# SCH_Irrigador-Autom_tico-Amanco_2026-02-.net
KiCad netlist of a schematic drawn in EasyEDA
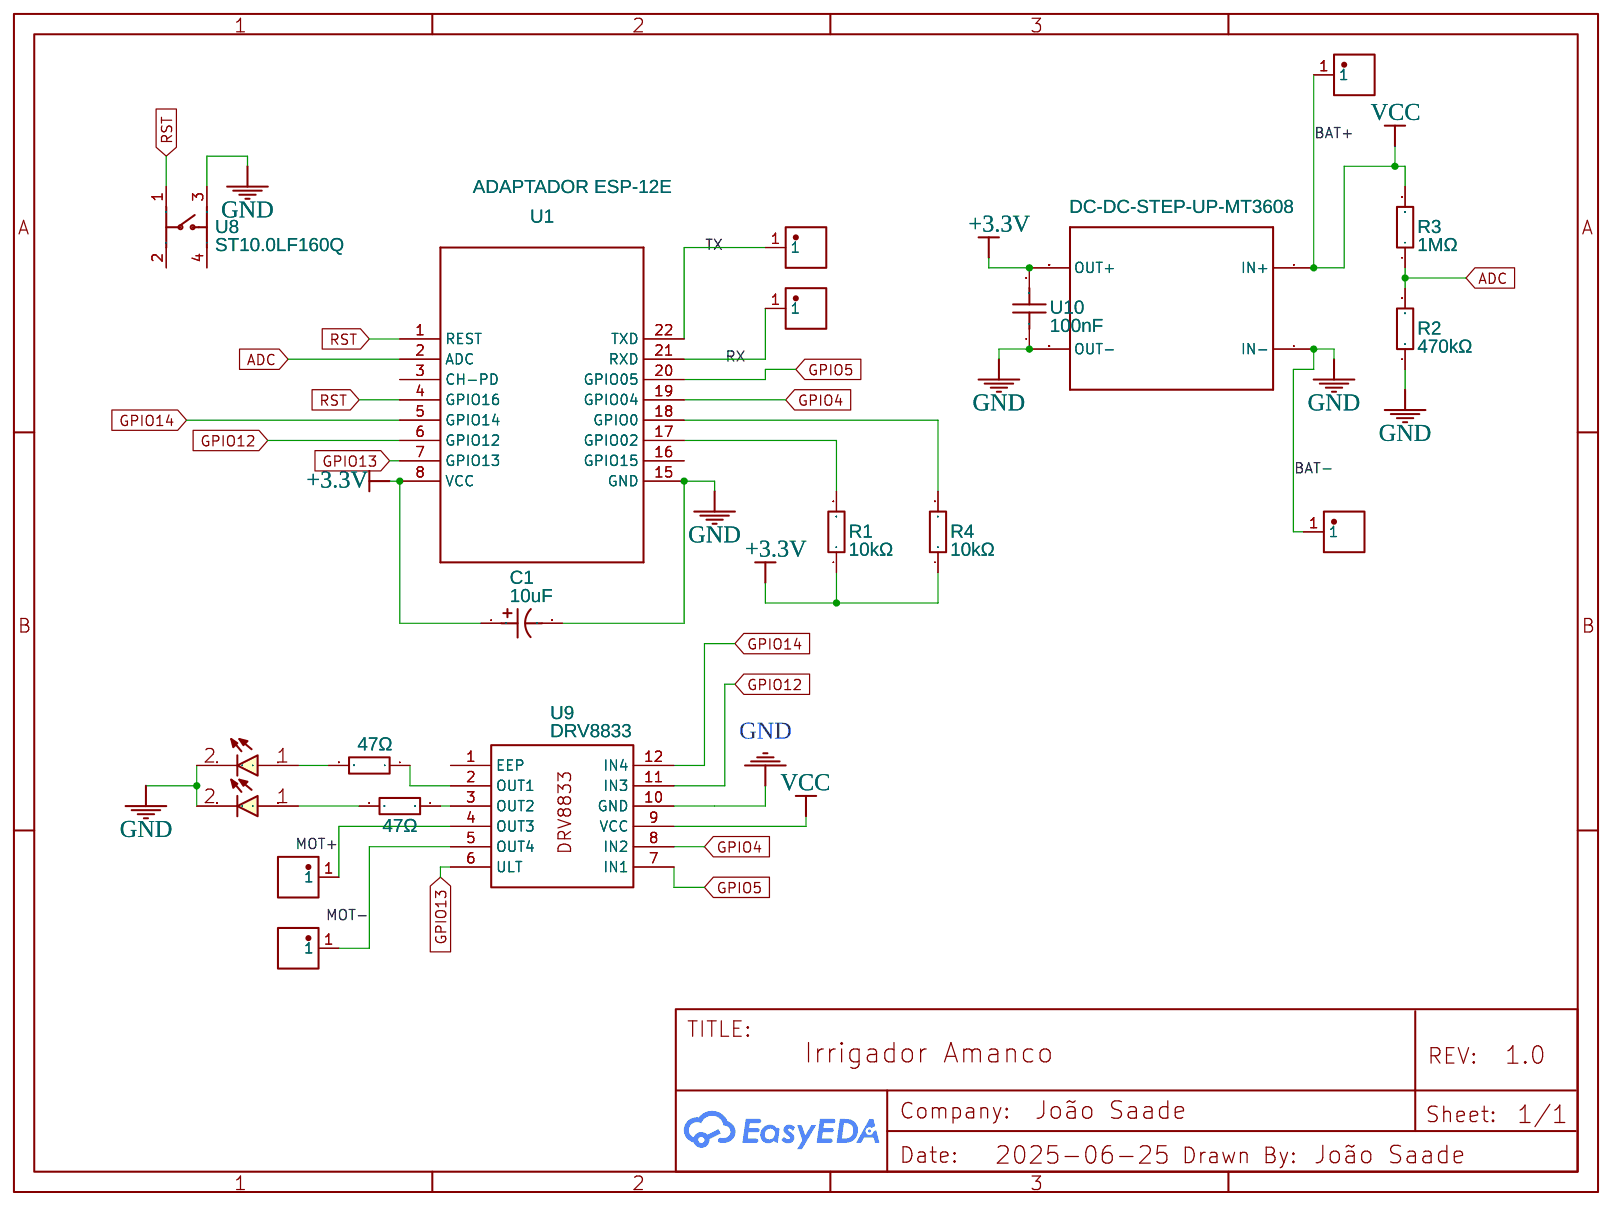
[diagram p0: schematic sheet]

(export (version "E")
  (design (tool "Eeschema 10.0.6"))
  (components
    (comp (ref "1") (value "DC-DC-STEP-UP-MT3608") (libsource (lib "") (part "DC-DC-STEP-UP-MT3608")))
    (comp (ref "C1")
      (value "10uF")
      (fields
        (field (name "Manufacturer Part") "NXA50V10M5*11 2.5TP")
        (field (name "Manufacturer") "SAMYOUNG(韩国三莹)")
      )
      (libsource (lib "") (part "NXA50V10M5*11 2.5TP"))
    )
    (comp (ref "LED1") (value "LED-5MM-GRE") (libsource (lib "") (part "LED-5MM-GRE")))
    (comp (ref "LED2") (value "LED-5MM-RED") (libsource (lib "") (part "LED-5MM-RED")))
    (comp (ref "R1")
      (value "10kΩ")
      (fields
        (field (name "Manufacturer Part") "CF1/4W-110KΩ±5% T52")
        (field (name "Manufacturer") "CCO(千志电子)")
      )
      (libsource (lib "") (part "CF1/4W-110KΩ±5% T52"))
    )
    (comp (ref "R2")
      (value "470kΩ")
      (fields
        (field (name "Manufacturer Part") "CF1/4W-110KΩ±5% T52")
        (field (name "Manufacturer") "CCO(千志电子)")
      )
      (libsource (lib "") (part "CF1/4W-110KΩ±5% T52"))
    )
    (comp (ref "R3")
      (value "1MΩ")
      (fields
        (field (name "Manufacturer Part") "CF1/4W-110KΩ±5% T52")
        (field (name "Manufacturer") "CCO(千志电子)")
      )
      (libsource (lib "") (part "CF1/4W-110KΩ±5% T52"))
    )
    (comp (ref "R4")
      (value "10kΩ")
      (fields
        (field (name "Manufacturer Part") "CF1/4W-110KΩ±5% T52")
        (field (name "Manufacturer") "CCO(千志电子)")
      )
      (libsource (lib "") (part "CF1/4W-110KΩ±5% T52"))
    )
    (comp (ref "R5")
      (value "47Ω")
      (fields
        (field (name "Manufacturer Part") "CF1/4W-110KΩ±5% T52")
        (field (name "Manufacturer") "CCO(千志电子)")
      )
      (libsource (lib "") (part "CF1/4W-110KΩ±5% T52_1"))
    )
    (comp (ref "R6")
      (value "47Ω")
      (fields
        (field (name "Manufacturer Part") "CF1/4W-110KΩ±5% T52")
        (field (name "Manufacturer") "CCO(千志电子)")
      )
      (libsource (lib "") (part "CF1/4W-110KΩ±5% T52_1"))
    )
    (comp (ref "U1") (value "ADAPTADOR ESP-12E") (libsource (lib "") (part "ADAPTADOR ESP-12E")))
    (comp (ref "U2")
      (value "P70-2200045")
      (fields (field (name "Manufacturer") "Harwin"))
      (libsource (lib "") (part "P70-2200045"))
    )
    (comp (ref "U3")
      (value "P70-2200045")
      (fields (field (name "Manufacturer") "Harwin"))
      (libsource (lib "") (part "P70-2200045"))
    )
    (comp (ref "U4")
      (value "P70-2200045")
      (fields (field (name "Manufacturer") "Harwin"))
      (libsource (lib "") (part "P70-2200045"))
    )
    (comp (ref "U5")
      (value "P70-2200045")
      (fields (field (name "Manufacturer") "Harwin"))
      (libsource (lib "") (part "P70-2200045"))
    )
    (comp (ref "U6")
      (value "P70-2200045")
      (fields (field (name "Manufacturer") "Harwin"))
      (libsource (lib "") (part "P70-2200045_1"))
    )
    (comp (ref "U7")
      (value "P70-2200045")
      (fields (field (name "Manufacturer") "Harwin"))
      (libsource (lib "") (part "P70-2200045_1"))
    )
    (comp (ref "U8")
      (value "ST10.0LF160Q")
      (fields (field (name "Manufacturer") "CIT Relay and Switch"))
      (libsource (lib "") (part "ST10.0LF160Q"))
    )
    (comp (ref "U9")
      (value "DRV8833")
      (fields (field (name "Manufacturer") "TI"))
      (libsource (lib "") (part "DRV8833"))
    )
    (comp (ref "U10")
      (value "100nF")
      (fields (field (name "Manufacturer Part") "K104K10X7RF5UH5") (field (name "Manufacturer") "VISHAY(威世)"))
      (libsource (lib "") (part "K104K10X7RF5UH5"))
    )
  )
  (nets
    (net (code "1") (name "+3.3V") (class "Default")
      (node (ref "1") (pin "OUT+") (pinfunction "OUT+_OUT+") (pintype "bidirectional"))
      (node (ref "C1") (pin "1") (pinfunction "1_1") (pintype "input"))
      (node (ref "R1") (pin "1") (pinfunction "1_1") (pintype "unspecified"))
      (node (ref "R4") (pin "1") (pinfunction "1_1") (pintype "unspecified"))
      (node (ref "U1") (pin "8") (pinfunction "VCC_8") (pintype "unspecified"))
      (node (ref "U10") (pin "2") (pinfunction "2_2") (pintype "unspecified"))
    )
    (net (code "2") (name "/MOT+") (class "Default")
      (node (ref "U6") (pin "1") (pinfunction "1_1") (pintype "unspecified"))
      (node (ref "U9") (pin "4") (pinfunction "OUT3_4") (pintype "unspecified"))
    )
    (net (code "3") (name "/MOT-") (class "Default")
      (node (ref "U7") (pin "1") (pinfunction "1_1") (pintype "unspecified"))
      (node (ref "U9") (pin "5") (pinfunction "OUT4_5") (pintype "unspecified"))
    )
    (net (code "4") (name "/RX") (class "Default")
      (node (ref "U1") (pin "21") (pinfunction "RXD_21") (pintype "unspecified"))
      (node (ref "U5") (pin "1") (pinfunction "1_1") (pintype "unspecified"))
    )
    (net (code "5") (name "/TX") (class "Default")
      (node (ref "U1") (pin "22") (pinfunction "TXD_22") (pintype "unspecified"))
      (node (ref "U4") (pin "1") (pinfunction "1_1") (pintype "unspecified"))
    )
    (net (code "6") (name "ADC") (class "Default")
      (node (ref "R2") (pin "2") (pinfunction "2_2") (pintype "unspecified"))
      (node (ref "R3") (pin "1") (pinfunction "1_1") (pintype "unspecified"))
      (node (ref "U1") (pin "2") (pinfunction "ADC_2") (pintype "unspecified"))
    )
    (net (code "7") (name "GND") (class "Default")
      (node (ref "1") (pin "IN-") (pinfunction "IN-_IN-") (pintype "bidirectional"))
      (node (ref "1") (pin "OUT-") (pinfunction "OUT-_OUT-") (pintype "bidirectional"))
      (node (ref "C1") (pin "2") (pinfunction "2_2") (pintype "input"))
      (node (ref "LED1") (pin "2") (pinfunction "K_2") (pintype "unspecified"))
      (node (ref "LED2") (pin "2") (pinfunction "K_2") (pintype "unspecified"))
      (node (ref "R2") (pin "1") (pinfunction "1_1") (pintype "unspecified"))
      (node (ref "U1") (pin "15") (pinfunction "GND_15") (pintype "unspecified"))
      (node (ref "U10") (pin "1") (pinfunction "1_1") (pintype "unspecified"))
      (node (ref "U2") (pin "1") (pinfunction "1_1") (pintype "unspecified"))
      (node (ref "U8") (pin "3") (pinfunction "3_3") (pintype "unspecified"))
      (node (ref "U9") (pin "10") (pinfunction "GND_10") (pintype "unspecified"))
    )
    (net (code "8") (name "GPIO4") (class "Default")
      (node (ref "U1") (pin "19") (pinfunction "GPIO04_19") (pintype "unspecified"))
      (node (ref "U9") (pin "8") (pinfunction "IN2_8") (pintype "unspecified"))
    )
    (net (code "9") (name "GPIO5") (class "Default")
      (node (ref "U1") (pin "20") (pinfunction "GPIO05_20") (pintype "unspecified"))
      (node (ref "U9") (pin "7") (pinfunction "IN1_7") (pintype "unspecified"))
    )
    (net (code "10") (name "GPIO12") (class "Default")
      (node (ref "U1") (pin "6") (pinfunction "GPIO12_6") (pintype "unspecified"))
      (node (ref "U9") (pin "11") (pinfunction "IN3_11") (pintype "unspecified"))
    )
    (net (code "11") (name "GPIO13") (class "Default")
      (node (ref "U1") (pin "7") (pinfunction "GPIO13_7") (pintype "unspecified"))
      (node (ref "U9") (pin "6") (pinfunction "ULT_6") (pintype "unspecified"))
    )
    (net (code "12") (name "GPIO14") (class "Default")
      (node (ref "U1") (pin "5") (pinfunction "GPIO14_5") (pintype "unspecified"))
      (node (ref "U9") (pin "12") (pinfunction "IN4_12") (pintype "unspecified"))
    )
    (net (code "13") (name "Net-(LED1-A)") (class "Default")
      (node (ref "LED1") (pin "1") (pinfunction "A_1") (pintype "unspecified"))
      (node (ref "R5") (pin "2") (pinfunction "2_2") (pintype "unspecified"))
    )
    (net (code "14") (name "Net-(LED2-A)") (class "Default")
      (node (ref "LED2") (pin "1") (pinfunction "A_1") (pintype "unspecified"))
      (node (ref "R6") (pin "2") (pinfunction "2_2") (pintype "unspecified"))
    )
    (net (code "15") (name "Net-(U1-GPIO0)") (class "Default")
      (node (ref "R4") (pin "2") (pinfunction "2_2") (pintype "unspecified"))
      (node (ref "U1") (pin "18") (pinfunction "GPIO0_18") (pintype "unspecified"))
    )
    (net (code "16") (name "Net-(U1-GPIO02)") (class "Default")
      (node (ref "R1") (pin "2") (pinfunction "2_2") (pintype "unspecified"))
      (node (ref "U1") (pin "17") (pinfunction "GPIO02_17") (pintype "unspecified"))
    )
    (net (code "17") (name "Net-(U9-OUT1)") (class "Default")
      (node (ref "R5") (pin "1") (pinfunction "1_1") (pintype "unspecified"))
      (node (ref "U9") (pin "2") (pinfunction "OUT1_2") (pintype "unspecified"))
    )
    (net (code "18") (name "Net-(U9-OUT2)") (class "Default")
      (node (ref "R6") (pin "1") (pinfunction "1_1") (pintype "unspecified"))
      (node (ref "U9") (pin "3") (pinfunction "OUT2_3") (pintype "unspecified"))
    )
    (net (code "19") (name "RST") (class "Default")
      (node (ref "U1") (pin "1") (pinfunction "REST_1") (pintype "unspecified"))
      (node (ref "U1") (pin "4") (pinfunction "GPIO16_4") (pintype "unspecified"))
      (node (ref "U8") (pin "1") (pinfunction "1_1") (pintype "unspecified"))
    )
    (net (code "20") (name "VCC") (class "Default")
      (node (ref "1") (pin "IN+") (pinfunction "IN+_IN+") (pintype "bidirectional"))
      (node (ref "R3") (pin "2") (pinfunction "2_2") (pintype "unspecified"))
      (node (ref "U3") (pin "1") (pinfunction "1_1") (pintype "unspecified"))
      (node (ref "U9") (pin "9") (pinfunction "VCC_9") (pintype "unspecified"))
    )
    (net (code "21") (name "unconnected-(U1-CH-PD-Pad3)") (class "Default")
      (node (ref "U1") (pin "3") (pinfunction "CH-PD_3") (pintype "unspecified"))
    )
    (net (code "22") (name "unconnected-(U1-GPIO15-Pad16)") (class "Default")
      (node (ref "U1") (pin "16") (pinfunction "GPIO15_16") (pintype "unspecified"))
    )
    (net (code "23") (name "unconnected-(U8-Pad2)") (class "Default")
      (node (ref "U8") (pin "2") (pinfunction "2_2") (pintype "unspecified"))
    )
    (net (code "24") (name "unconnected-(U8-Pad4)") (class "Default")
      (node (ref "U8") (pin "4") (pinfunction "4_4") (pintype "unspecified"))
    )
    (net (code "25") (name "unconnected-(U9-EEP-Pad1)") (class "Default")
      (node (ref "U9") (pin "1") (pinfunction "EEP_1") (pintype "unspecified"))
    )
  )
)
